# Backplane.net
KiCad netlist of a schematic drawn in Altium Designer
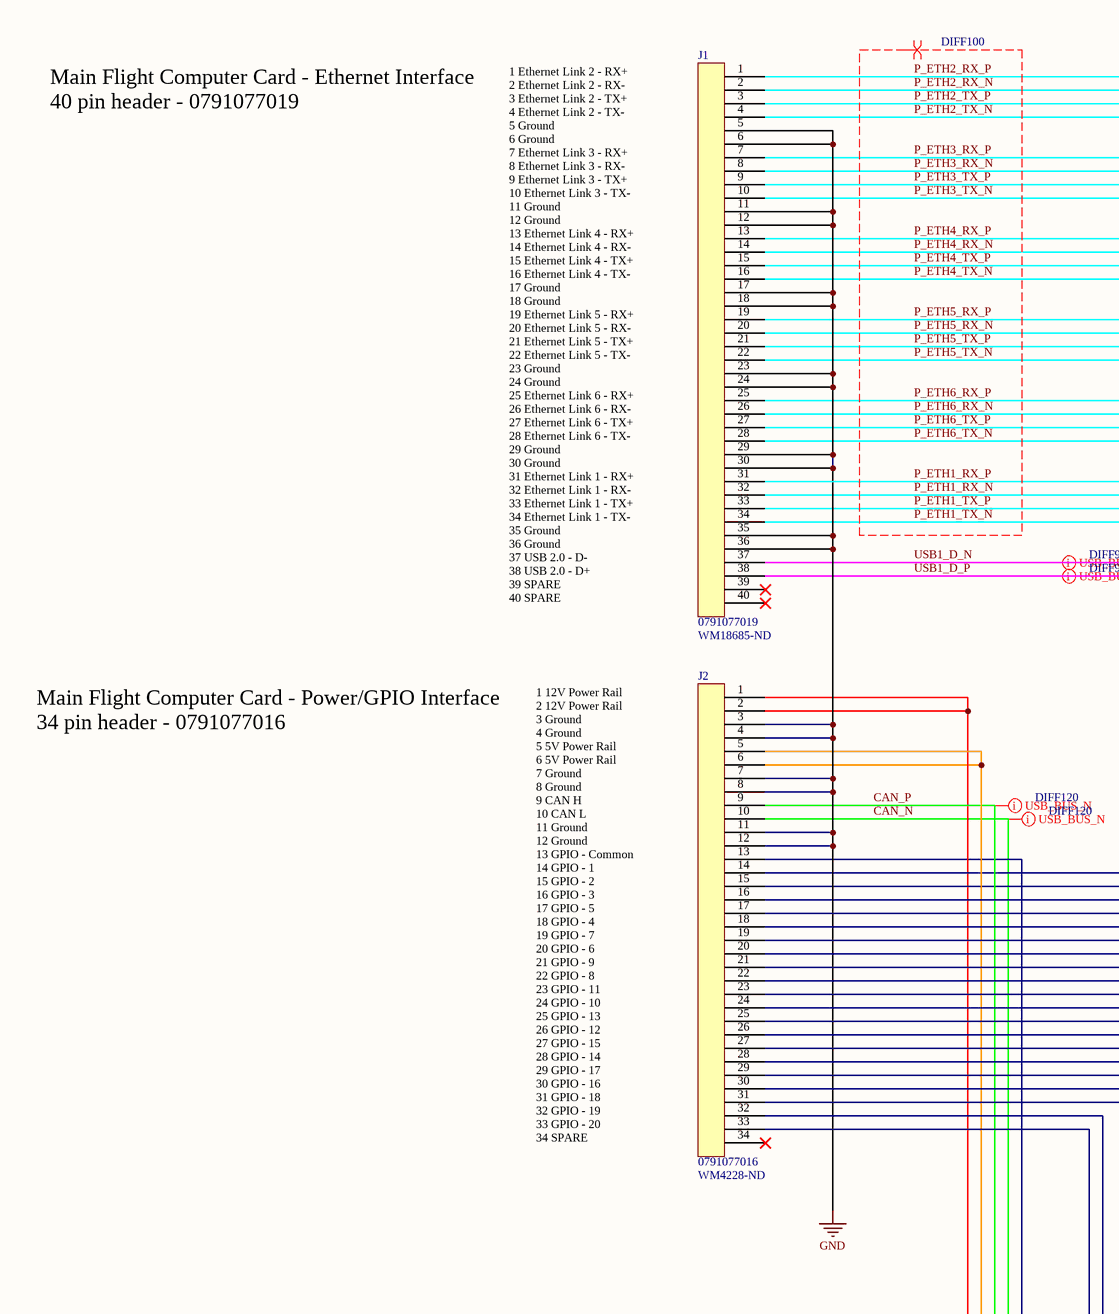
[diagram p0: Backplane.SchDoc, top left]
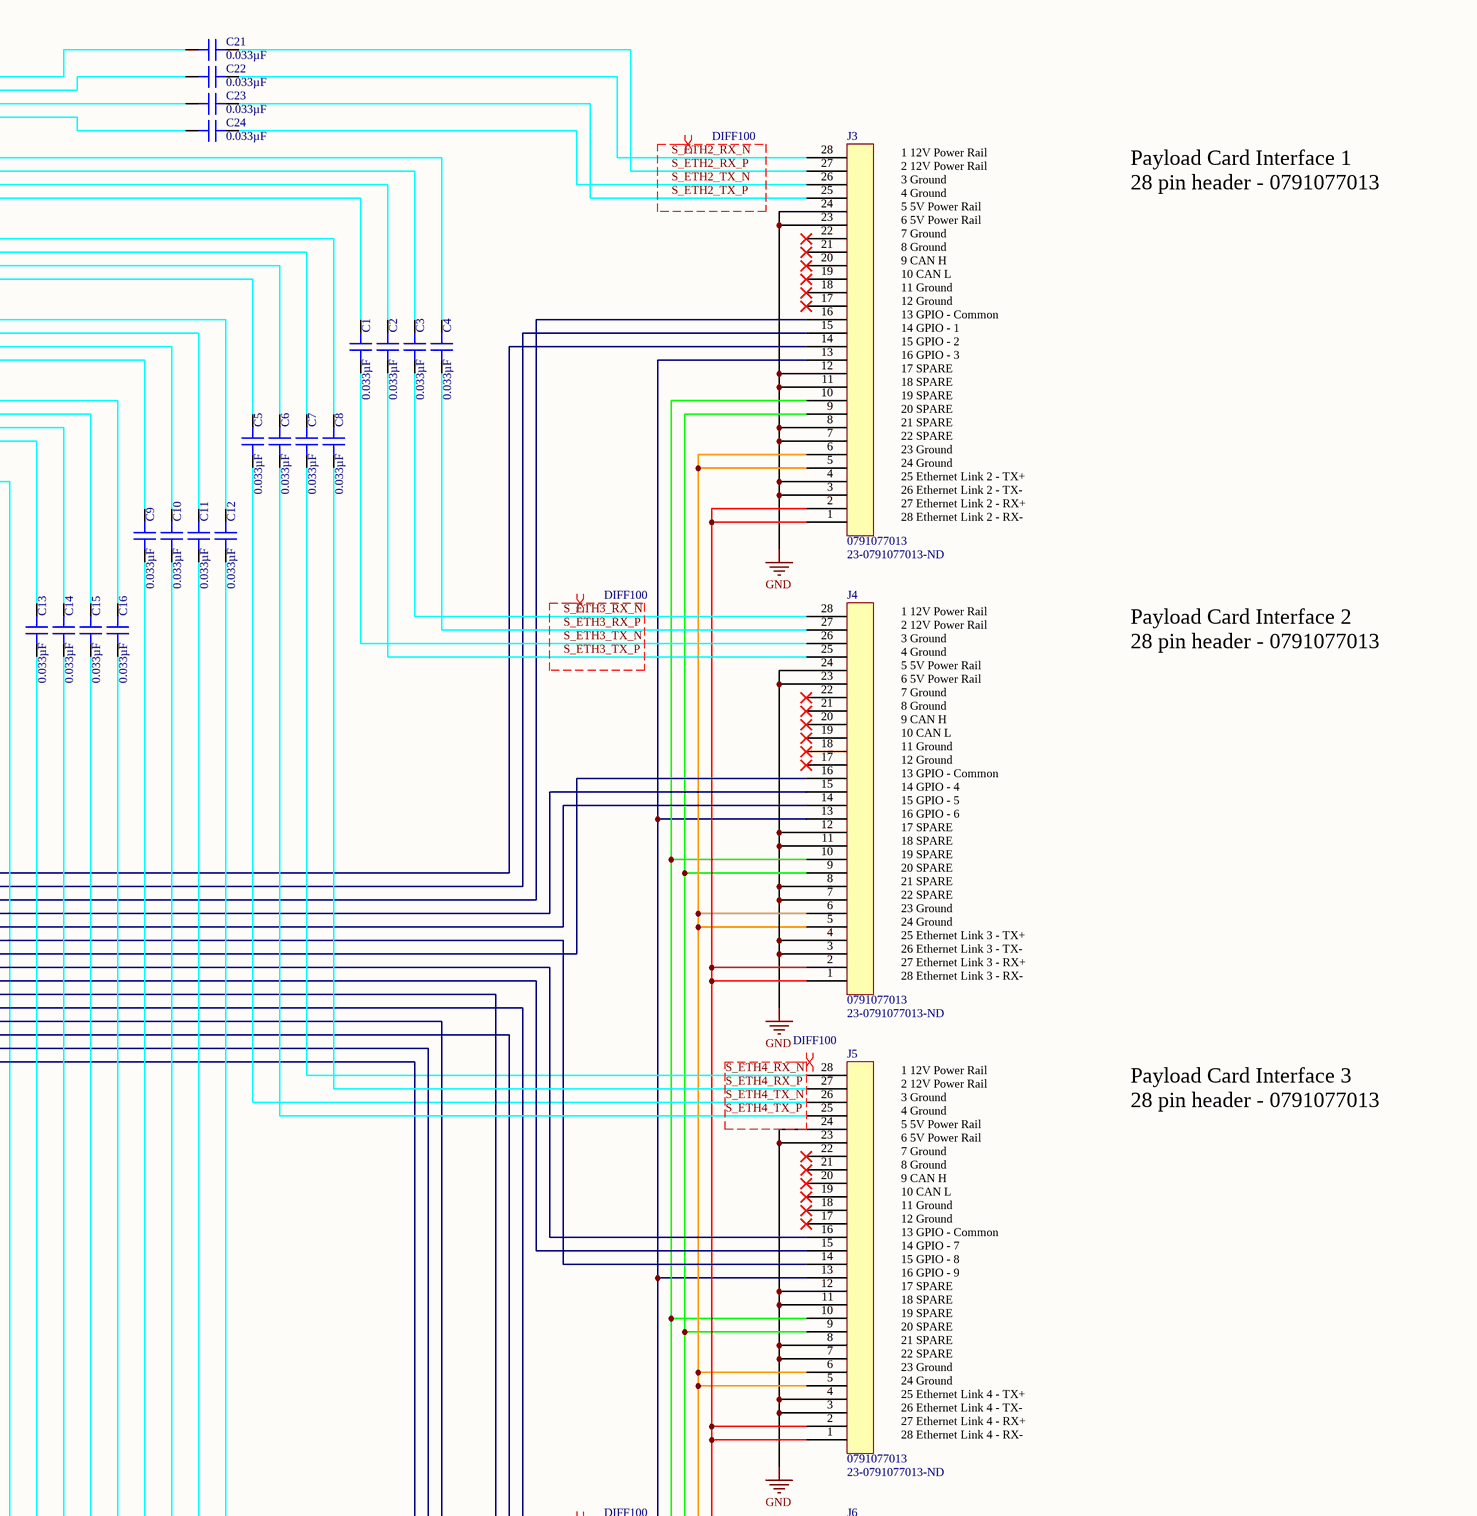
[diagram p1: Backplane.SchDoc, top right]
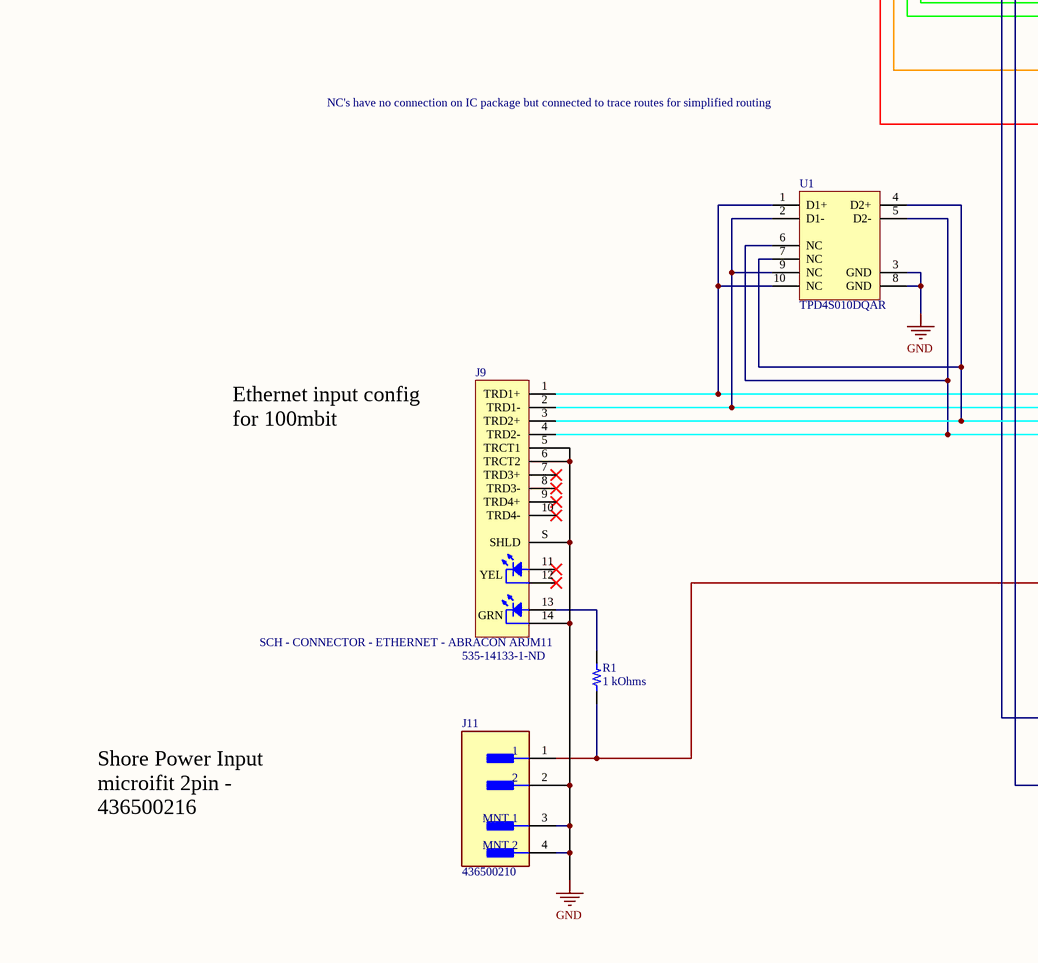
[diagram p2: Backplane.SchDoc, bottom left]
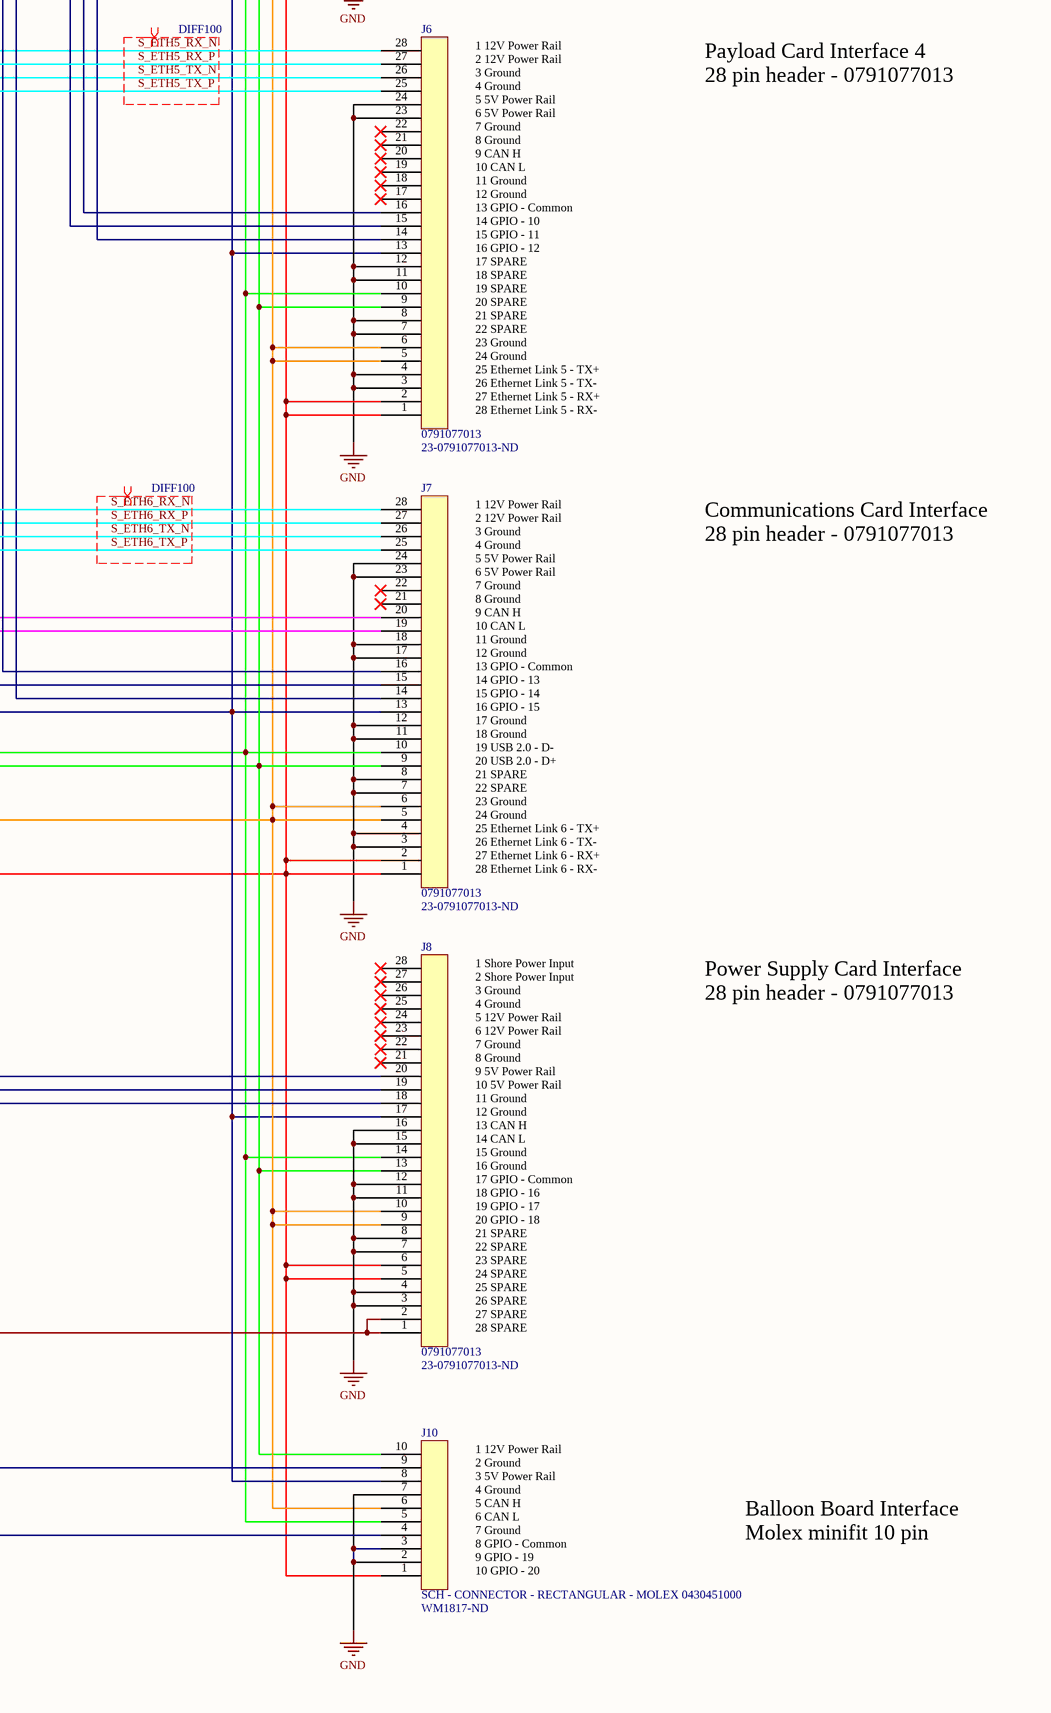
[diagram p3: Backplane.SchDoc, bottom right]

(export (version "E")
  (design (tool "Eeschema 10.0.6"))
  (components
    (comp (ref "C1")
      (value "0.033µF")
      (footprint "CAP 0603_1608")
      (description "CAP CER 0.033UF 50V X7R 0603")
      (fields
        (field (name "PART NUMBER") "CL10B333KB8NFNC")
        (field (name "MANUFACTURER") "Samsung Electro-Mechanics")
      )
      (libsource (lib "Celestial Altium Library - altium_library") (part "Capacitor"))
    )
    (comp (ref "C2")
      (value "0.033µF")
      (footprint "CAP 0603_1608")
      (description "CAP CER 0.033UF 50V X7R 0603")
      (fields
        (field (name "PART NUMBER") "CL10B333KB8NFNC")
        (field (name "MANUFACTURER") "Samsung Electro-Mechanics")
      )
      (libsource (lib "Celestial Altium Library - altium_library") (part "Capacitor"))
    )
    (comp (ref "C3")
      (value "0.033µF")
      (footprint "CAP 0603_1608")
      (description "CAP CER 0.033UF 50V X7R 0603")
      (fields
        (field (name "PART NUMBER") "CL10B333KB8NFNC")
        (field (name "MANUFACTURER") "Samsung Electro-Mechanics")
      )
      (libsource (lib "Celestial Altium Library - altium_library") (part "Capacitor"))
    )
    (comp (ref "C4")
      (value "0.033µF")
      (footprint "CAP 0603_1608")
      (description "CAP CER 0.033UF 50V X7R 0603")
      (fields
        (field (name "PART NUMBER") "CL10B333KB8NFNC")
        (field (name "MANUFACTURER") "Samsung Electro-Mechanics")
      )
      (libsource (lib "Celestial Altium Library - altium_library") (part "Capacitor"))
    )
    (comp (ref "C5")
      (value "0.033µF")
      (footprint "CAP 0603_1608")
      (description "CAP CER 0.033UF 50V X7R 0603")
      (fields
        (field (name "PART NUMBER") "CL10B333KB8NFNC")
        (field (name "MANUFACTURER") "Samsung Electro-Mechanics")
      )
      (libsource (lib "Celestial Altium Library - altium_library") (part "Capacitor"))
    )
    (comp (ref "C6")
      (value "0.033µF")
      (footprint "CAP 0603_1608")
      (description "CAP CER 0.033UF 50V X7R 0603")
      (fields
        (field (name "PART NUMBER") "CL10B333KB8NFNC")
        (field (name "MANUFACTURER") "Samsung Electro-Mechanics")
      )
      (libsource (lib "Celestial Altium Library - altium_library") (part "Capacitor"))
    )
    (comp (ref "C7")
      (value "0.033µF")
      (footprint "CAP 0603_1608")
      (description "CAP CER 0.033UF 50V X7R 0603")
      (fields
        (field (name "PART NUMBER") "CL10B333KB8NFNC")
        (field (name "MANUFACTURER") "Samsung Electro-Mechanics")
      )
      (libsource (lib "Celestial Altium Library - altium_library") (part "Capacitor"))
    )
    (comp (ref "C8")
      (value "0.033µF")
      (footprint "CAP 0603_1608")
      (description "CAP CER 0.033UF 50V X7R 0603")
      (fields
        (field (name "PART NUMBER") "CL10B333KB8NFNC")
        (field (name "MANUFACTURER") "Samsung Electro-Mechanics")
      )
      (libsource (lib "Celestial Altium Library - altium_library") (part "Capacitor"))
    )
    (comp (ref "C9")
      (value "0.033µF")
      (footprint "CAP 0603_1608")
      (description "CAP CER 0.033UF 50V X7R 0603")
      (fields
        (field (name "PART NUMBER") "CL10B333KB8NFNC")
        (field (name "MANUFACTURER") "Samsung Electro-Mechanics")
      )
      (libsource (lib "Celestial Altium Library - altium_library") (part "Capacitor"))
    )
    (comp (ref "C10")
      (value "0.033µF")
      (footprint "CAP 0603_1608")
      (description "CAP CER 0.033UF 50V X7R 0603")
      (fields
        (field (name "PART NUMBER") "CL10B333KB8NFNC")
        (field (name "MANUFACTURER") "Samsung Electro-Mechanics")
      )
      (libsource (lib "Celestial Altium Library - altium_library") (part "Capacitor"))
    )
    (comp (ref "C11")
      (value "0.033µF")
      (footprint "CAP 0603_1608")
      (description "CAP CER 0.033UF 50V X7R 0603")
      (fields
        (field (name "PART NUMBER") "CL10B333KB8NFNC")
        (field (name "MANUFACTURER") "Samsung Electro-Mechanics")
      )
      (libsource (lib "Celestial Altium Library - altium_library") (part "Capacitor"))
    )
    (comp (ref "C12")
      (value "0.033µF")
      (footprint "CAP 0603_1608")
      (description "CAP CER 0.033UF 50V X7R 0603")
      (fields
        (field (name "PART NUMBER") "CL10B333KB8NFNC")
        (field (name "MANUFACTURER") "Samsung Electro-Mechanics")
      )
      (libsource (lib "Celestial Altium Library - altium_library") (part "Capacitor"))
    )
    (comp (ref "C13")
      (value "0.033µF")
      (footprint "CAP 0603_1608")
      (description "CAP CER 0.033UF 50V X7R 0603")
      (fields
        (field (name "PART NUMBER") "CL10B333KB8NFNC")
        (field (name "MANUFACTURER") "Samsung Electro-Mechanics")
      )
      (libsource (lib "Celestial Altium Library - altium_library") (part "Capacitor"))
    )
    (comp (ref "C14")
      (value "0.033µF")
      (footprint "CAP 0603_1608")
      (description "CAP CER 0.033UF 50V X7R 0603")
      (fields
        (field (name "PART NUMBER") "CL10B333KB8NFNC")
        (field (name "MANUFACTURER") "Samsung Electro-Mechanics")
      )
      (libsource (lib "Celestial Altium Library - altium_library") (part "Capacitor"))
    )
    (comp (ref "C15")
      (value "0.033µF")
      (footprint "CAP 0603_1608")
      (description "CAP CER 0.033UF 50V X7R 0603")
      (fields
        (field (name "PART NUMBER") "CL10B333KB8NFNC")
        (field (name "MANUFACTURER") "Samsung Electro-Mechanics")
      )
      (libsource (lib "Celestial Altium Library - altium_library") (part "Capacitor"))
    )
    (comp (ref "C16")
      (value "0.033µF")
      (footprint "CAP 0603_1608")
      (description "CAP CER 0.033UF 50V X7R 0603")
      (fields
        (field (name "PART NUMBER") "CL10B333KB8NFNC")
        (field (name "MANUFACTURER") "Samsung Electro-Mechanics")
      )
      (libsource (lib "Celestial Altium Library - altium_library") (part "Capacitor"))
    )
    (comp (ref "C21")
      (value "0.033µF")
      (footprint "CAP 0603_1608")
      (description "CAP CER 0.033UF 50V X7R 0603")
      (fields
        (field (name "PART NUMBER") "CL10B333KB8NFNC")
        (field (name "MANUFACTURER") "Samsung Electro-Mechanics")
      )
      (libsource (lib "Celestial Altium Library - altium_library") (part "Capacitor"))
    )
    (comp (ref "C22")
      (value "0.033µF")
      (footprint "CAP 0603_1608")
      (description "CAP CER 0.033UF 50V X7R 0603")
      (fields
        (field (name "PART NUMBER") "CL10B333KB8NFNC")
        (field (name "MANUFACTURER") "Samsung Electro-Mechanics")
      )
      (libsource (lib "Celestial Altium Library - altium_library") (part "Capacitor"))
    )
    (comp (ref "C23")
      (value "0.033µF")
      (footprint "CAP 0603_1608")
      (description "CAP CER 0.033UF 50V X7R 0603")
      (fields
        (field (name "PART NUMBER") "CL10B333KB8NFNC")
        (field (name "MANUFACTURER") "Samsung Electro-Mechanics")
      )
      (libsource (lib "Celestial Altium Library - altium_library") (part "Capacitor"))
    )
    (comp (ref "C24")
      (value "0.033µF")
      (footprint "CAP 0603_1608")
      (description "CAP CER 0.033UF 50V X7R 0603")
      (fields
        (field (name "PART NUMBER") "CL10B333KB8NFNC")
        (field (name "MANUFACTURER") "Samsung Electro-Mechanics")
      )
      (libsource (lib "Celestial Altium Library - altium_library") (part "Capacitor"))
    )
    (comp (ref "J1")
      (value "0791077019")
      (footprint "0791077019")
      (fields (field (name "SUPPLIER PART NUMBER 1") "WM18685-ND"))
      (libsource (lib "HAB_Connectors") (part "0791077019"))
    )
    (comp (ref "J2")
      (value "0791077016")
      (footprint "0791077016")
      (fields (field (name "SUPPLIER PART NUMBER 1") "WM4228-ND"))
      (libsource (lib "HAB_Connectors") (part "0791077016"))
    )
    (comp (ref "J3")
      (value "0791077013")
      (footprint "0791077013")
      (fields (field (name "SUPPLIER PART NUMBER 1") "23-0791077013-ND"))
      (libsource (lib "HAB_Connectors") (part "0791077013"))
    )
    (comp (ref "J4")
      (value "0791077013")
      (footprint "0791077013")
      (fields (field (name "SUPPLIER PART NUMBER 1") "23-0791077013-ND"))
      (libsource (lib "HAB_Connectors") (part "0791077013"))
    )
    (comp (ref "J5")
      (value "0791077013")
      (footprint "0791077013")
      (fields (field (name "SUPPLIER PART NUMBER 1") "23-0791077013-ND"))
      (libsource (lib "HAB_Connectors") (part "0791077013"))
    )
    (comp (ref "J6")
      (value "0791077013")
      (footprint "0791077013")
      (fields (field (name "SUPPLIER PART NUMBER 1") "23-0791077013-ND"))
      (libsource (lib "HAB_Connectors") (part "0791077013"))
    )
    (comp (ref "J7")
      (value "0791077013")
      (footprint "0791077013")
      (fields (field (name "SUPPLIER PART NUMBER 1") "23-0791077013-ND"))
      (libsource (lib "HAB_Connectors") (part "0791077013"))
    )
    (comp (ref "J8")
      (value "0791077013")
      (footprint "0791077013")
      (fields (field (name "SUPPLIER PART NUMBER 1") "23-0791077013-ND"))
      (libsource (lib "HAB_Connectors") (part "0791077013"))
    )
    (comp (ref "J9")
      (value "SCH - CONNECTOR - ETHERNET - ABRACON ARJM11")
      (footprint "PCB - CONNECTOR - MODULAR - ETHERNET - ABRACON ARJM11")
      (fields (field (name "SUPPLIER PART NUMBER 1") "535-14133-1-ND"))
      (libsource (lib "HAB_Connectors") (part "SCH - CONNECTOR - ETHERNET - ABRACON ARJM11"))
    )
    (comp (ref "J10")
      (value "SCH - CONNECTOR - RECTANGULAR - MOLEX 0430451000")
      (footprint "PCB - CONNECTOR - RECTANGULAR - MOLEX 0430451000")
      (fields (field (name "SUPPLIER PART NUMBER 1") "WM1817-ND"))
      (libsource (lib "HAB_Connectors") (part "SCH - CONNECTOR - RECTANGULAR - MOLEX 0430451000"))
    )
    (comp (ref "J11")
      (value "436500210")
      (footprint "FP-436500210-MFG")
      (description "CONN HEADER SMD R/A 2POS 3MM")
      (fields
        (field (name "MANUFACTURER") "Molex")
        (field (name "OCTOPART") "https://octopart.com/43650-0210-molex-298097")
      )
      (libsource (lib "Altium Content Vault") (part "029478cb6d4f2fad0cd2a245525ee6d"))
    )
    (comp (ref "R1")
      (value "1 kOhms")
      (footprint "RES 0603_1608")
      (description "RES 1K OHM 1% 1/8W 0603")
      (fields
        (field (name "PART NUMBER") "RNCP0603FTD1K00")
        (field (name "MANUFACTURER") "Stackpole Electronics Inc")
      )
      (libsource (lib "Celestial Altium Library - altium_library") (part "Resistor"))
    )
    (comp (ref "U1")
      (value "TPD4S010DQAR")
      (footprint "DQA0010A_V")
      (fields (field (name "MANUFACTURER") "Texas Instruments"))
      (libsource (lib "Altium Content Vault") (part "TI-TPD4S010-SON_DQA-10"))
    )
  )
  (nets
    (net (code "1") (name "/CAN_N") (class "Default")
      (node (ref "J10") (pin "5") (pintype "passive"))
      (node (ref "J2") (pin "10") (pintype "passive"))
      (node (ref "J3") (pin "10") (pintype "passive"))
      (node (ref "J4") (pin "10") (pintype "passive"))
      (node (ref "J5") (pin "10") (pintype "passive"))
      (node (ref "J6") (pin "10") (pintype "passive"))
      (node (ref "J7") (pin "10") (pintype "passive"))
      (node (ref "J8") (pin "14") (pintype "passive"))
    )
    (net (code "2") (name "/CAN_P") (class "Default")
      (node (ref "J10") (pin "10") (pintype "passive"))
      (node (ref "J2") (pin "9") (pintype "passive"))
      (node (ref "J3") (pin "9") (pintype "passive"))
      (node (ref "J4") (pin "9") (pintype "passive"))
      (node (ref "J5") (pin "9") (pintype "passive"))
      (node (ref "J6") (pin "9") (pintype "passive"))
      (node (ref "J7") (pin "9") (pintype "passive"))
      (node (ref "J8") (pin "13") (pintype "passive"))
    )
    (net (code "3") (name "/P_ETH1_RX_N") (class "Default")
      (node (ref "J1") (pin "32") (pintype "passive"))
      (node (ref "J9") (pin "4") (pinfunction "TRD2-_4") (pintype "passive"))
      (node (ref "U1") (pin "5") (pinfunction "D2-_5") (pintype "passive"))
      (node (ref "U1") (pin "6") (pinfunction "NC_6") (pintype "passive"))
    )
    (net (code "4") (name "/P_ETH1_RX_P") (class "Default")
      (node (ref "J1") (pin "31") (pintype "passive"))
      (node (ref "J9") (pin "3") (pinfunction "TRD2+_3") (pintype "passive"))
      (node (ref "U1") (pin "4") (pinfunction "D2+_4") (pintype "passive"))
      (node (ref "U1") (pin "7") (pinfunction "NC_7") (pintype "passive"))
    )
    (net (code "5") (name "/P_ETH1_TX_N") (class "Default")
      (node (ref "J1") (pin "34") (pintype "passive"))
      (node (ref "J9") (pin "2") (pinfunction "TRD1-_2") (pintype "passive"))
      (node (ref "U1") (pin "2") (pinfunction "D1-_2") (pintype "passive"))
      (node (ref "U1") (pin "9") (pinfunction "NC_9") (pintype "passive"))
    )
    (net (code "6") (name "/P_ETH1_TX_P") (class "Default")
      (node (ref "J1") (pin "33") (pintype "passive"))
      (node (ref "J9") (pin "1") (pinfunction "TRD1+_1") (pintype "passive"))
      (node (ref "U1") (pin "1") (pinfunction "D1+_1") (pintype "passive"))
      (node (ref "U1") (pin "10") (pinfunction "NC_10") (pintype "passive"))
    )
    (net (code "7") (name "/P_ETH2_RX_N") (class "Default")
      (node (ref "C22") (pin "2") (pinfunction "2_2") (pintype "passive"))
      (node (ref "J1") (pin "2") (pintype "passive"))
    )
    (net (code "8") (name "/P_ETH2_RX_P") (class "Default")
      (node (ref "C21") (pin "2") (pinfunction "2_2") (pintype "passive"))
      (node (ref "J1") (pin "1") (pintype "passive"))
    )
    (net (code "9") (name "/P_ETH2_TX_N") (class "Default")
      (node (ref "C24") (pin "2") (pinfunction "2_2") (pintype "passive"))
      (node (ref "J1") (pin "4") (pintype "passive"))
    )
    (net (code "10") (name "/P_ETH2_TX_P") (class "Default")
      (node (ref "C23") (pin "2") (pinfunction "2_2") (pintype "passive"))
      (node (ref "J1") (pin "3") (pintype "passive"))
    )
    (net (code "11") (name "/P_ETH3_RX_N") (class "Default")
      (node (ref "C3") (pin "2") (pinfunction "2_2") (pintype "passive"))
      (node (ref "J1") (pin "8") (pintype "passive"))
    )
    (net (code "12") (name "/P_ETH3_RX_P") (class "Default")
      (node (ref "C4") (pin "2") (pinfunction "2_2") (pintype "passive"))
      (node (ref "J1") (pin "7") (pintype "passive"))
    )
    (net (code "13") (name "/P_ETH3_TX_N") (class "Default")
      (node (ref "C1") (pin "2") (pinfunction "2_2") (pintype "passive"))
      (node (ref "J1") (pin "10") (pintype "passive"))
    )
    (net (code "14") (name "/P_ETH3_TX_P") (class "Default")
      (node (ref "C2") (pin "2") (pinfunction "2_2") (pintype "passive"))
      (node (ref "J1") (pin "9") (pintype "passive"))
    )
    (net (code "15") (name "/P_ETH4_RX_N") (class "Default")
      (node (ref "C7") (pin "2") (pinfunction "2_2") (pintype "passive"))
      (node (ref "J1") (pin "14") (pintype "passive"))
    )
    (net (code "16") (name "/P_ETH4_RX_P") (class "Default")
      (node (ref "C8") (pin "2") (pinfunction "2_2") (pintype "passive"))
      (node (ref "J1") (pin "13") (pintype "passive"))
    )
    (net (code "17") (name "/P_ETH4_TX_N") (class "Default")
      (node (ref "C5") (pin "2") (pinfunction "2_2") (pintype "passive"))
      (node (ref "J1") (pin "16") (pintype "passive"))
    )
    (net (code "18") (name "/P_ETH4_TX_P") (class "Default")
      (node (ref "C6") (pin "2") (pinfunction "2_2") (pintype "passive"))
      (node (ref "J1") (pin "15") (pintype "passive"))
    )
    (net (code "19") (name "/P_ETH5_RX_N") (class "Default")
      (node (ref "C11") (pin "2") (pinfunction "2_2") (pintype "passive"))
      (node (ref "J1") (pin "20") (pintype "passive"))
    )
    (net (code "20") (name "/P_ETH5_RX_P") (class "Default")
      (node (ref "C12") (pin "2") (pinfunction "2_2") (pintype "passive"))
      (node (ref "J1") (pin "19") (pintype "passive"))
    )
    (net (code "21") (name "/P_ETH5_TX_N") (class "Default")
      (node (ref "C9") (pin "2") (pinfunction "2_2") (pintype "passive"))
      (node (ref "J1") (pin "22") (pintype "passive"))
    )
    (net (code "22") (name "/P_ETH5_TX_P") (class "Default")
      (node (ref "C10") (pin "2") (pinfunction "2_2") (pintype "passive"))
      (node (ref "J1") (pin "21") (pintype "passive"))
    )
    (net (code "23") (name "/P_ETH6_RX_N") (class "Default")
      (node (ref "C15") (pin "2") (pinfunction "2_2") (pintype "passive"))
      (node (ref "J1") (pin "26") (pintype "passive"))
    )
    (net (code "24") (name "/P_ETH6_RX_P") (class "Default")
      (node (ref "C16") (pin "2") (pinfunction "2_2") (pintype "passive"))
      (node (ref "J1") (pin "25") (pintype "passive"))
    )
    (net (code "25") (name "/P_ETH6_TX_N") (class "Default")
      (node (ref "C13") (pin "2") (pinfunction "2_2") (pintype "passive"))
      (node (ref "J1") (pin "28") (pintype "passive"))
    )
    (net (code "26") (name "/P_ETH6_TX_P") (class "Default")
      (node (ref "C14") (pin "2") (pinfunction "2_2") (pintype "passive"))
      (node (ref "J1") (pin "27") (pintype "passive"))
    )
    (net (code "27") (name "/S_ETH2_RX_N") (class "Default")
      (node (ref "C22") (pin "1") (pinfunction "1_1") (pintype "passive"))
      (node (ref "J3") (pin "28") (pintype "passive"))
    )
    (net (code "28") (name "/S_ETH2_RX_P") (class "Default")
      (node (ref "C21") (pin "1") (pinfunction "1_1") (pintype "passive"))
      (node (ref "J3") (pin "27") (pintype "passive"))
    )
    (net (code "29") (name "/S_ETH2_TX_N") (class "Default")
      (node (ref "C24") (pin "1") (pinfunction "1_1") (pintype "passive"))
      (node (ref "J3") (pin "26") (pintype "passive"))
    )
    (net (code "30") (name "/S_ETH2_TX_P") (class "Default")
      (node (ref "C23") (pin "1") (pinfunction "1_1") (pintype "passive"))
      (node (ref "J3") (pin "25") (pintype "passive"))
    )
    (net (code "31") (name "/S_ETH3_RX_N") (class "Default")
      (node (ref "C3") (pin "1") (pinfunction "1_1") (pintype "passive"))
      (node (ref "J4") (pin "28") (pintype "passive"))
    )
    (net (code "32") (name "/S_ETH3_RX_P") (class "Default")
      (node (ref "C4") (pin "1") (pinfunction "1_1") (pintype "passive"))
      (node (ref "J4") (pin "27") (pintype "passive"))
    )
    (net (code "33") (name "/S_ETH3_TX_N") (class "Default")
      (node (ref "C1") (pin "1") (pinfunction "1_1") (pintype "passive"))
      (node (ref "J4") (pin "26") (pintype "passive"))
    )
    (net (code "34") (name "/S_ETH3_TX_P") (class "Default")
      (node (ref "C2") (pin "1") (pinfunction "1_1") (pintype "passive"))
      (node (ref "J4") (pin "25") (pintype "passive"))
    )
    (net (code "35") (name "/S_ETH4_RX_N") (class "Default")
      (node (ref "C7") (pin "1") (pinfunction "1_1") (pintype "passive"))
      (node (ref "J5") (pin "28") (pintype "passive"))
    )
    (net (code "36") (name "/S_ETH4_RX_P") (class "Default")
      (node (ref "C8") (pin "1") (pinfunction "1_1") (pintype "passive"))
      (node (ref "J5") (pin "27") (pintype "passive"))
    )
    (net (code "37") (name "/S_ETH4_TX_N") (class "Default")
      (node (ref "C5") (pin "1") (pinfunction "1_1") (pintype "passive"))
      (node (ref "J5") (pin "26") (pintype "passive"))
    )
    (net (code "38") (name "/S_ETH4_TX_P") (class "Default")
      (node (ref "C6") (pin "1") (pinfunction "1_1") (pintype "passive"))
      (node (ref "J5") (pin "25") (pintype "passive"))
    )
    (net (code "39") (name "/S_ETH5_RX_N") (class "Default")
      (node (ref "C11") (pin "1") (pinfunction "1_1") (pintype "passive"))
      (node (ref "J6") (pin "28") (pintype "passive"))
    )
    (net (code "40") (name "/S_ETH5_RX_P") (class "Default")
      (node (ref "C12") (pin "1") (pinfunction "1_1") (pintype "passive"))
      (node (ref "J6") (pin "27") (pintype "passive"))
    )
    (net (code "41") (name "/S_ETH5_TX_N") (class "Default")
      (node (ref "C9") (pin "1") (pinfunction "1_1") (pintype "passive"))
      (node (ref "J6") (pin "26") (pintype "passive"))
    )
    (net (code "42") (name "/S_ETH5_TX_P") (class "Default")
      (node (ref "C10") (pin "1") (pinfunction "1_1") (pintype "passive"))
      (node (ref "J6") (pin "25") (pintype "passive"))
    )
    (net (code "43") (name "/S_ETH6_RX_N") (class "Default")
      (node (ref "C15") (pin "1") (pinfunction "1_1") (pintype "passive"))
      (node (ref "J7") (pin "28") (pintype "passive"))
    )
    (net (code "44") (name "/S_ETH6_RX_P") (class "Default")
      (node (ref "C16") (pin "1") (pinfunction "1_1") (pintype "passive"))
      (node (ref "J7") (pin "27") (pintype "passive"))
    )
    (net (code "45") (name "/S_ETH6_TX_N") (class "Default")
      (node (ref "C13") (pin "1") (pinfunction "1_1") (pintype "passive"))
      (node (ref "J7") (pin "26") (pintype "passive"))
    )
    (net (code "46") (name "/S_ETH6_TX_P") (class "Default")
      (node (ref "C14") (pin "1") (pinfunction "1_1") (pintype "passive"))
      (node (ref "J7") (pin "25") (pintype "passive"))
    )
    (net (code "47") (name "/USB1_D_N") (class "Default")
      (node (ref "J1") (pin "37") (pintype "passive"))
      (node (ref "J7") (pin "19") (pintype "passive"))
    )
    (net (code "48") (name "/USB1_D_P") (class "Default")
      (node (ref "J1") (pin "38") (pintype "passive"))
      (node (ref "J7") (pin "20") (pintype "passive"))
    )
    (net (code "49") (name "GND") (class "Default")
      (node (ref "J1") (pin "11") (pintype "passive"))
      (node (ref "J1") (pin "12") (pintype "passive"))
      (node (ref "J1") (pin "17") (pintype "passive"))
      (node (ref "J1") (pin "18") (pintype "passive"))
      (node (ref "J1") (pin "23") (pintype "passive"))
      (node (ref "J1") (pin "24") (pintype "passive"))
      (node (ref "J1") (pin "29") (pintype "passive"))
      (node (ref "J1") (pin "30") (pintype "passive"))
      (node (ref "J1") (pin "35") (pintype "passive"))
      (node (ref "J1") (pin "36") (pintype "passive"))
      (node (ref "J1") (pin "5") (pintype "passive"))
      (node (ref "J1") (pin "6") (pintype "passive"))
      (node (ref "J10") (pin "2") (pintype "passive"))
      (node (ref "J10") (pin "3") (pintype "passive"))
      (node (ref "J10") (pin "7") (pintype "passive"))
      (node (ref "J11") (pin "2") (pinfunction "2_2") (pintype "passive"))
      (node (ref "J11") (pin "3") (pinfunction "MNT_1_3") (pintype "passive"))
      (node (ref "J11") (pin "4") (pinfunction "MNT_2_4") (pintype "passive"))
      (node (ref "J2") (pin "11") (pintype "passive"))
      (node (ref "J2") (pin "12") (pintype "passive"))
      (node (ref "J2") (pin "3") (pintype "passive"))
      (node (ref "J2") (pin "4") (pintype "passive"))
      (node (ref "J2") (pin "7") (pintype "passive"))
      (node (ref "J2") (pin "8") (pintype "passive"))
      (node (ref "J3") (pin "11") (pintype "passive"))
      (node (ref "J3") (pin "12") (pintype "passive"))
      (node (ref "J3") (pin "23") (pintype "passive"))
      (node (ref "J3") (pin "24") (pintype "passive"))
      (node (ref "J3") (pin "3") (pintype "passive"))
      (node (ref "J3") (pin "4") (pintype "passive"))
      (node (ref "J3") (pin "7") (pintype "passive"))
      (node (ref "J3") (pin "8") (pintype "passive"))
      (node (ref "J4") (pin "11") (pintype "passive"))
      (node (ref "J4") (pin "12") (pintype "passive"))
      (node (ref "J4") (pin "23") (pintype "passive"))
      (node (ref "J4") (pin "24") (pintype "passive"))
      (node (ref "J4") (pin "3") (pintype "passive"))
      (node (ref "J4") (pin "4") (pintype "passive"))
      (node (ref "J4") (pin "7") (pintype "passive"))
      (node (ref "J4") (pin "8") (pintype "passive"))
      (node (ref "J5") (pin "11") (pintype "passive"))
      (node (ref "J5") (pin "12") (pintype "passive"))
      (node (ref "J5") (pin "23") (pintype "passive"))
      (node (ref "J5") (pin "24") (pintype "passive"))
      (node (ref "J5") (pin "3") (pintype "passive"))
      (node (ref "J5") (pin "4") (pintype "passive"))
      (node (ref "J5") (pin "7") (pintype "passive"))
      (node (ref "J5") (pin "8") (pintype "passive"))
      (node (ref "J6") (pin "11") (pintype "passive"))
      (node (ref "J6") (pin "12") (pintype "passive"))
      (node (ref "J6") (pin "23") (pintype "passive"))
      (node (ref "J6") (pin "24") (pintype "passive"))
      (node (ref "J6") (pin "3") (pintype "passive"))
      (node (ref "J6") (pin "4") (pintype "passive"))
      (node (ref "J6") (pin "7") (pintype "passive"))
      (node (ref "J6") (pin "8") (pintype "passive"))
      (node (ref "J7") (pin "11") (pintype "passive"))
      (node (ref "J7") (pin "12") (pintype "passive"))
      (node (ref "J7") (pin "17") (pintype "passive"))
      (node (ref "J7") (pin "18") (pintype "passive"))
      (node (ref "J7") (pin "23") (pintype "passive"))
      (node (ref "J7") (pin "24") (pintype "passive"))
      (node (ref "J7") (pin "3") (pintype "passive"))
      (node (ref "J7") (pin "4") (pintype "passive"))
      (node (ref "J7") (pin "7") (pintype "passive"))
      (node (ref "J7") (pin "8") (pintype "passive"))
      (node (ref "J8") (pin "11") (pintype "passive"))
      (node (ref "J8") (pin "12") (pintype "passive"))
      (node (ref "J8") (pin "15") (pintype "passive"))
      (node (ref "J8") (pin "16") (pintype "passive"))
      (node (ref "J8") (pin "3") (pintype "passive"))
      (node (ref "J8") (pin "4") (pintype "passive"))
      (node (ref "J8") (pin "7") (pintype "passive"))
      (node (ref "J8") (pin "8") (pintype "passive"))
      (node (ref "J9") (pin "14") (pinfunction "L4_14") (pintype "passive"))
      (node (ref "J9") (pin "5") (pinfunction "TRCT1_5") (pintype "passive"))
      (node (ref "J9") (pin "6") (pinfunction "TRCT2_6") (pintype "passive"))
      (node (ref "J9") (pin "S") (pinfunction "SHLD_S") (pintype "passive"))
      (node (ref "U1") (pin "3") (pinfunction "GND_3") (pintype "power_in"))
      (node (ref "U1") (pin "8") (pinfunction "GND_8") (pintype "power_in"))
    )
    (net (code "50") (name "Net-(J2-Pad14)") (class "Default")
      (node (ref "J2") (pin "14") (pintype "passive"))
      (node (ref "J3") (pin "14") (pintype "passive"))
    )
    (net (code "51") (name "Net-(J2-Pad15)") (class "Default")
      (node (ref "J2") (pin "15") (pintype "passive"))
      (node (ref "J3") (pin "15") (pintype "passive"))
    )
    (net (code "52") (name "Net-(J2-Pad16)") (class "Default")
      (node (ref "J2") (pin "16") (pintype "passive"))
      (node (ref "J3") (pin "16") (pintype "passive"))
    )
    (net (code "53") (name "Net-(J2-Pad17)") (class "Default")
      (node (ref "J2") (pin "17") (pintype "passive"))
      (node (ref "J4") (pin "15") (pintype "passive"))
    )
    (net (code "54") (name "Net-(J2-Pad18)") (class "Default")
      (node (ref "J2") (pin "18") (pintype "passive"))
      (node (ref "J4") (pin "14") (pintype "passive"))
    )
    (net (code "55") (name "Net-(J2-Pad19)") (class "Default")
      (node (ref "J2") (pin "19") (pintype "passive"))
      (node (ref "J5") (pin "14") (pintype "passive"))
    )
    (net (code "56") (name "Net-(J2-Pad20)") (class "Default")
      (node (ref "J2") (pin "20") (pintype "passive"))
      (node (ref "J4") (pin "16") (pintype "passive"))
    )
    (net (code "57") (name "Net-(J2-Pad21)") (class "Default")
      (node (ref "J2") (pin "21") (pintype "passive"))
      (node (ref "J5") (pin "16") (pintype "passive"))
    )
    (net (code "58") (name "Net-(J2-Pad22)") (class "Default")
      (node (ref "J2") (pin "22") (pintype "passive"))
      (node (ref "J5") (pin "15") (pintype "passive"))
    )
    (net (code "59") (name "Net-(J2-Pad23)") (class "Default")
      (node (ref "J2") (pin "23") (pintype "passive"))
      (node (ref "J6") (pin "15") (pintype "passive"))
    )
    (net (code "60") (name "Net-(J2-Pad24)") (class "Default")
      (node (ref "J2") (pin "24") (pintype "passive"))
      (node (ref "J6") (pin "14") (pintype "passive"))
    )
    (net (code "61") (name "Net-(J2-Pad25)") (class "Default")
      (node (ref "J2") (pin "25") (pintype "passive"))
      (node (ref "J7") (pin "14") (pintype "passive"))
    )
    (net (code "62") (name "Net-(J2-Pad26)") (class "Default")
      (node (ref "J2") (pin "26") (pintype "passive"))
      (node (ref "J6") (pin "16") (pintype "passive"))
    )
    (net (code "63") (name "Net-(J2-Pad27)") (class "Default")
      (node (ref "J2") (pin "27") (pintype "passive"))
      (node (ref "J7") (pin "16") (pintype "passive"))
    )
    (net (code "64") (name "Net-(J2-Pad28)") (class "Default")
      (node (ref "J2") (pin "28") (pintype "passive"))
      (node (ref "J7") (pin "15") (pintype "passive"))
    )
    (net (code "65") (name "Net-(J2-Pad29)") (class "Default")
      (node (ref "J2") (pin "29") (pintype "passive"))
      (node (ref "J8") (pin "19") (pintype "passive"))
    )
    (net (code "66") (name "Net-(J2-Pad30)") (class "Default")
      (node (ref "J2") (pin "30") (pintype "passive"))
      (node (ref "J8") (pin "18") (pintype "passive"))
    )
    (net (code "67") (name "Net-(J2-Pad31)") (class "Default")
      (node (ref "J2") (pin "31") (pintype "passive"))
      (node (ref "J8") (pin "20") (pintype "passive"))
    )
    (net (code "68") (name "Net-(J9-L3)") (class "Default")
      (node (ref "J9") (pin "13") (pinfunction "L3_13") (pintype "passive"))
      (node (ref "R1") (pin "1") (pinfunction "1_1") (pintype "passive"))
    )
    (net (code "69") (name "Net-(J10-Pad1)") (class "Default")
      (node (ref "J10") (pin "1") (pintype "passive"))
      (node (ref "J2") (pin "1") (pintype "passive"))
      (node (ref "J2") (pin "2") (pintype "passive"))
      (node (ref "J3") (pin "1") (pintype "passive"))
      (node (ref "J3") (pin "2") (pintype "passive"))
      (node (ref "J4") (pin "1") (pintype "passive"))
      (node (ref "J4") (pin "2") (pintype "passive"))
      (node (ref "J5") (pin "1") (pintype "passive"))
      (node (ref "J5") (pin "2") (pintype "passive"))
      (node (ref "J6") (pin "1") (pintype "passive"))
      (node (ref "J6") (pin "2") (pintype "passive"))
      (node (ref "J7") (pin "1") (pintype "passive"))
      (node (ref "J7") (pin "2") (pintype "passive"))
      (node (ref "J8") (pin "5") (pintype "passive"))
      (node (ref "J8") (pin "6") (pintype "passive"))
    )
    (net (code "70") (name "Net-(J10-Pad4)") (class "Default")
      (node (ref "J10") (pin "4") (pintype "passive"))
      (node (ref "J2") (pin "32") (pintype "passive"))
    )
    (net (code "71") (name "Net-(J10-Pad6)") (class "Default")
      (node (ref "J10") (pin "6") (pintype "passive"))
      (node (ref "J2") (pin "5") (pintype "passive"))
      (node (ref "J2") (pin "6") (pintype "passive"))
      (node (ref "J3") (pin "5") (pintype "passive"))
      (node (ref "J3") (pin "6") (pintype "passive"))
      (node (ref "J4") (pin "5") (pintype "passive"))
      (node (ref "J4") (pin "6") (pintype "passive"))
      (node (ref "J5") (pin "5") (pintype "passive"))
      (node (ref "J5") (pin "6") (pintype "passive"))
      (node (ref "J6") (pin "5") (pintype "passive"))
      (node (ref "J6") (pin "6") (pintype "passive"))
      (node (ref "J7") (pin "5") (pintype "passive"))
      (node (ref "J7") (pin "6") (pintype "passive"))
      (node (ref "J8") (pin "10") (pintype "passive"))
      (node (ref "J8") (pin "9") (pintype "passive"))
    )
    (net (code "72") (name "Net-(J10-Pad8)") (class "Default")
      (node (ref "J10") (pin "8") (pintype "passive"))
      (node (ref "J2") (pin "13") (pintype "passive"))
      (node (ref "J3") (pin "13") (pintype "passive"))
      (node (ref "J4") (pin "13") (pintype "passive"))
      (node (ref "J5") (pin "13") (pintype "passive"))
      (node (ref "J6") (pin "13") (pintype "passive"))
      (node (ref "J7") (pin "13") (pintype "passive"))
      (node (ref "J8") (pin "17") (pintype "passive"))
    )
    (net (code "73") (name "Net-(J10-Pad9)") (class "Default")
      (node (ref "J10") (pin "9") (pintype "passive"))
      (node (ref "J2") (pin "33") (pintype "passive"))
    )
    (net (code "74") (name "Net-(J11-Pad1)") (class "Default")
      (node (ref "J11") (pin "1") (pinfunction "1_1") (pintype "passive"))
      (node (ref "J8") (pin "1") (pintype "passive"))
      (node (ref "J8") (pin "2") (pintype "passive"))
      (node (ref "R1") (pin "2") (pinfunction "2_2") (pintype "passive"))
    )
    (net (code "75") (name "unconnected-(J1-Pad39)") (class "Default")
      (node (ref "J1") (pin "39") (pintype "passive+no_connect"))
    )
    (net (code "76") (name "unconnected-(J1-Pad40)") (class "Default")
      (node (ref "J1") (pin "40") (pintype "passive+no_connect"))
    )
    (net (code "77") (name "unconnected-(J2-Pad34)") (class "Default")
      (node (ref "J2") (pin "34") (pintype "passive+no_connect"))
    )
    (net (code "78") (name "unconnected-(J3-Pad17)") (class "Default")
      (node (ref "J3") (pin "17") (pintype "passive+no_connect"))
    )
    (net (code "79") (name "unconnected-(J3-Pad18)") (class "Default")
      (node (ref "J3") (pin "18") (pintype "passive+no_connect"))
    )
    (net (code "80") (name "unconnected-(J3-Pad19)") (class "Default")
      (node (ref "J3") (pin "19") (pintype "passive+no_connect"))
    )
    (net (code "81") (name "unconnected-(J3-Pad20)") (class "Default")
      (node (ref "J3") (pin "20") (pintype "passive+no_connect"))
    )
    (net (code "82") (name "unconnected-(J3-Pad21)") (class "Default")
      (node (ref "J3") (pin "21") (pintype "passive+no_connect"))
    )
    (net (code "83") (name "unconnected-(J3-Pad22)") (class "Default")
      (node (ref "J3") (pin "22") (pintype "passive+no_connect"))
    )
    (net (code "84") (name "unconnected-(J4-Pad17)") (class "Default")
      (node (ref "J4") (pin "17") (pintype "passive+no_connect"))
    )
    (net (code "85") (name "unconnected-(J4-Pad18)") (class "Default")
      (node (ref "J4") (pin "18") (pintype "passive+no_connect"))
    )
    (net (code "86") (name "unconnected-(J4-Pad19)") (class "Default")
      (node (ref "J4") (pin "19") (pintype "passive+no_connect"))
    )
    (net (code "87") (name "unconnected-(J4-Pad20)") (class "Default")
      (node (ref "J4") (pin "20") (pintype "passive+no_connect"))
    )
    (net (code "88") (name "unconnected-(J4-Pad21)") (class "Default")
      (node (ref "J4") (pin "21") (pintype "passive+no_connect"))
    )
    (net (code "89") (name "unconnected-(J4-Pad22)") (class "Default")
      (node (ref "J4") (pin "22") (pintype "passive+no_connect"))
    )
    (net (code "90") (name "unconnected-(J5-Pad17)") (class "Default")
      (node (ref "J5") (pin "17") (pintype "passive+no_connect"))
    )
    (net (code "91") (name "unconnected-(J5-Pad18)") (class "Default")
      (node (ref "J5") (pin "18") (pintype "passive+no_connect"))
    )
    (net (code "92") (name "unconnected-(J5-Pad19)") (class "Default")
      (node (ref "J5") (pin "19") (pintype "passive+no_connect"))
    )
    (net (code "93") (name "unconnected-(J5-Pad20)") (class "Default")
      (node (ref "J5") (pin "20") (pintype "passive+no_connect"))
    )
    (net (code "94") (name "unconnected-(J5-Pad21)") (class "Default")
      (node (ref "J5") (pin "21") (pintype "passive+no_connect"))
    )
    (net (code "95") (name "unconnected-(J5-Pad22)") (class "Default")
      (node (ref "J5") (pin "22") (pintype "passive+no_connect"))
    )
    (net (code "96") (name "unconnected-(J6-Pad17)") (class "Default")
      (node (ref "J6") (pin "17") (pintype "passive+no_connect"))
    )
    (net (code "97") (name "unconnected-(J6-Pad18)") (class "Default")
      (node (ref "J6") (pin "18") (pintype "passive+no_connect"))
    )
    (net (code "98") (name "unconnected-(J6-Pad19)") (class "Default")
      (node (ref "J6") (pin "19") (pintype "passive+no_connect"))
    )
    (net (code "99") (name "unconnected-(J6-Pad20)") (class "Default")
      (node (ref "J6") (pin "20") (pintype "passive+no_connect"))
    )
    (net (code "100") (name "unconnected-(J6-Pad21)") (class "Default")
      (node (ref "J6") (pin "21") (pintype "passive+no_connect"))
    )
    (net (code "101") (name "unconnected-(J6-Pad22)") (class "Default")
      (node (ref "J6") (pin "22") (pintype "passive+no_connect"))
    )
    (net (code "102") (name "unconnected-(J7-Pad21)") (class "Default")
      (node (ref "J7") (pin "21") (pintype "passive+no_connect"))
    )
    (net (code "103") (name "unconnected-(J7-Pad22)") (class "Default")
      (node (ref "J7") (pin "22") (pintype "passive+no_connect"))
    )
    (net (code "104") (name "unconnected-(J8-Pad21)") (class "Default")
      (node (ref "J8") (pin "21") (pintype "passive+no_connect"))
    )
    (net (code "105") (name "unconnected-(J8-Pad22)") (class "Default")
      (node (ref "J8") (pin "22") (pintype "passive+no_connect"))
    )
    (net (code "106") (name "unconnected-(J8-Pad23)") (class "Default")
      (node (ref "J8") (pin "23") (pintype "passive+no_connect"))
    )
    (net (code "107") (name "unconnected-(J8-Pad24)") (class "Default")
      (node (ref "J8") (pin "24") (pintype "passive+no_connect"))
    )
    (net (code "108") (name "unconnected-(J8-Pad25)") (class "Default")
      (node (ref "J8") (pin "25") (pintype "passive+no_connect"))
    )
    (net (code "109") (name "unconnected-(J8-Pad26)") (class "Default")
      (node (ref "J8") (pin "26") (pintype "passive+no_connect"))
    )
    (net (code "110") (name "unconnected-(J8-Pad27)") (class "Default")
      (node (ref "J8") (pin "27") (pintype "passive+no_connect"))
    )
    (net (code "111") (name "unconnected-(J8-Pad28)") (class "Default")
      (node (ref "J8") (pin "28") (pintype "passive+no_connect"))
    )
    (net (code "112") (name "unconnected-(J9-L1-Pad11)") (class "Default")
      (node (ref "J9") (pin "11") (pinfunction "L1_11") (pintype "passive+no_connect"))
    )
    (net (code "113") (name "unconnected-(J9-L2-Pad12)") (class "Default")
      (node (ref "J9") (pin "12") (pinfunction "L2_12") (pintype "passive+no_connect"))
    )
    (net (code "114") (name "unconnected-(J9-TRD3+-Pad7)") (class "Default")
      (node (ref "J9") (pin "7") (pinfunction "TRD3+_7") (pintype "passive+no_connect"))
    )
    (net (code "115") (name "unconnected-(J9-TRD3--Pad8)") (class "Default")
      (node (ref "J9") (pin "8") (pinfunction "TRD3-_8") (pintype "passive+no_connect"))
    )
    (net (code "116") (name "unconnected-(J9-TRD4+-Pad9)") (class "Default")
      (node (ref "J9") (pin "9") (pinfunction "TRD4+_9") (pintype "passive+no_connect"))
    )
    (net (code "117") (name "unconnected-(J9-TRD4--Pad10)") (class "Default")
      (node (ref "J9") (pin "10") (pinfunction "TRD4-_10") (pintype "passive+no_connect"))
    )
  )
)
